# cc1101-adapter.net
KiCad netlist of a schematic drawn in EAGLE
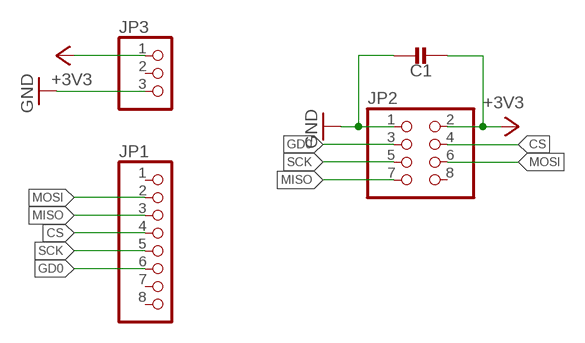
[diagram p0: schematic, sheet 1]

(export (version "E")
  (design (tool "Eeschema 10.0.6"))
  (components
    (comp (ref "C1")
      (value "CAPACITOR0805_CAP")
      (footprint "eagle-import:0805_CAP")
      (libsource (lib "eagle-import") (part "CAPACITOR0805_CAP"))
    )
    (comp (ref "JP1")
      (value "PINHD-1X8")
      (footprint "eagle-import:1X08")
      (libsource (lib "eagle-import") (part "PINHD-1X8"))
    )
    (comp (ref "JP2")
      (value "PINHD-2X4")
      (footprint "eagle-import:2X04")
      (libsource (lib "eagle-import") (part "PINHD-2X4"))
    )
    (comp (ref "JP3")
      (value "PINHD-1X3")
      (footprint "eagle-import:1X03")
      (libsource (lib "eagle-import") (part "PINHD-1X3"))
    )
  )
  (nets
    (net (code "1") (name "+3V3") (class "Default")
      (node (ref "C1") (pin "P$2") (pinfunction "2_P$2") (pintype "bidirectional"))
      (node (ref "JP2") (pin "2") (pinfunction "2_2") (pintype "passive"))
      (node (ref "JP3") (pin "1") (pinfunction "1_1") (pintype "passive"))
    )
    (net (code "2") (name "CS") (class "Default")
      (node (ref "JP1") (pin "4") (pinfunction "4_4") (pintype "passive"))
      (node (ref "JP2") (pin "4") (pinfunction "4_4") (pintype "passive"))
    )
    (net (code "3") (name "GD0") (class "Default")
      (node (ref "JP1") (pin "6") (pinfunction "6_6") (pintype "passive"))
      (node (ref "JP2") (pin "3") (pinfunction "3_3") (pintype "passive"))
    )
    (net (code "4") (name "GND") (class "Default")
      (node (ref "C1") (pin "P$1") (pinfunction "1_P$1") (pintype "bidirectional"))
      (node (ref "JP2") (pin "1") (pinfunction "1_1") (pintype "passive"))
      (node (ref "JP3") (pin "3") (pinfunction "3_3") (pintype "passive"))
    )
    (net (code "5") (name "MISO") (class "Default")
      (node (ref "JP1") (pin "3") (pinfunction "3_3") (pintype "passive"))
      (node (ref "JP2") (pin "7") (pinfunction "7_7") (pintype "passive"))
    )
    (net (code "6") (name "MOSI") (class "Default")
      (node (ref "JP1") (pin "2") (pinfunction "2_2") (pintype "passive"))
      (node (ref "JP2") (pin "6") (pinfunction "6_6") (pintype "passive"))
    )
    (net (code "7") (name "SCK") (class "Default")
      (node (ref "JP1") (pin "5") (pinfunction "5_5") (pintype "passive"))
      (node (ref "JP2") (pin "5") (pinfunction "5_5") (pintype "passive"))
    )
    (net (code "8") (name "unconnected-(JP1-Pad1)") (class "Default")
      (node (ref "JP1") (pin "1") (pinfunction "1_1") (pintype "passive"))
    )
    (net (code "9") (name "unconnected-(JP1-Pad7)") (class "Default")
      (node (ref "JP1") (pin "7") (pinfunction "7_7") (pintype "passive"))
    )
    (net (code "10") (name "unconnected-(JP1-Pad8)") (class "Default")
      (node (ref "JP1") (pin "8") (pinfunction "8_8") (pintype "passive"))
    )
    (net (code "11") (name "unconnected-(JP2-Pad8)") (class "Default")
      (node (ref "JP2") (pin "8") (pinfunction "8_8") (pintype "passive"))
    )
    (net (code "12") (name "unconnected-(JP3-Pad2)") (class "Default")
      (node (ref "JP3") (pin "2") (pinfunction "2_2") (pintype "passive"))
    )
  )
)
